# Controller.net
KiCad netlist of a schematic drawn in Altium Designer
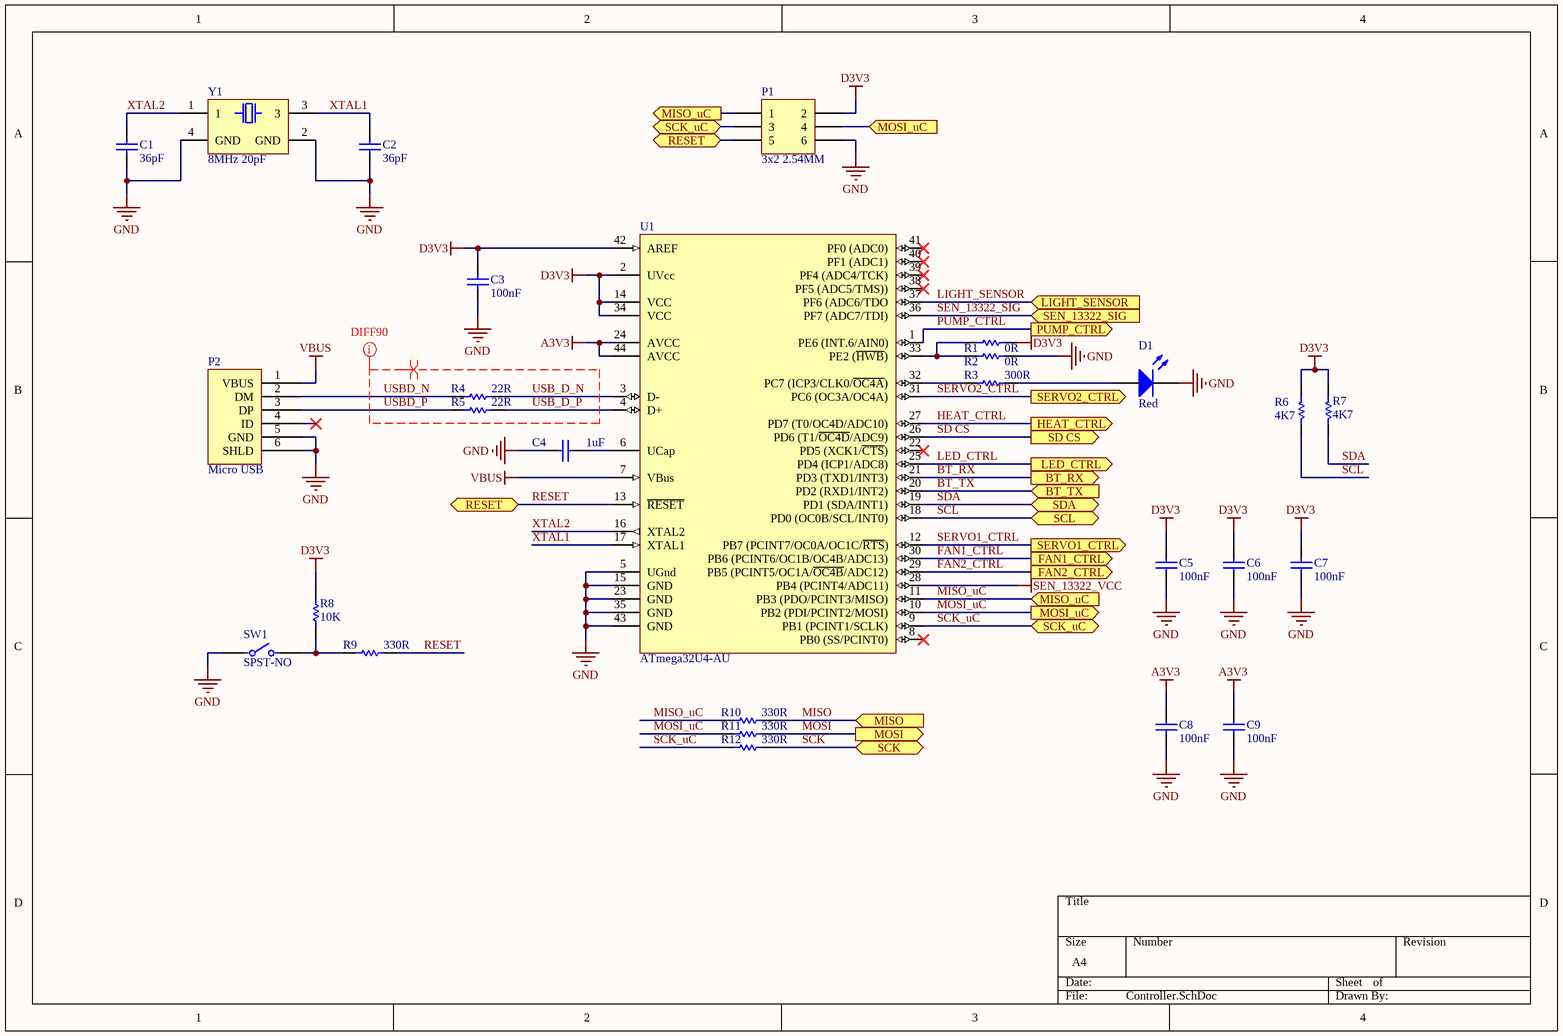
[diagram p0: Controller.SchDoc]

(export (version "E")
  (design (tool "Eeschema 10.0.6"))
  (components
    (comp (ref "C1")
      (value "36pF")
      (footprint "CAP0603")
      (description "Capacitor")
      (fields (field (name "PUBLISHER") "Altium Limited"))
      (libsource (lib "Taiv") (part "Capacitor"))
    )
    (comp (ref "C2")
      (value "36pF")
      (footprint "CAP0603")
      (description "Capacitor")
      (fields (field (name "PUBLISHER") "Altium Limited"))
      (libsource (lib "Taiv") (part "Capacitor"))
    )
    (comp (ref "C3")
      (value "100nF")
      (footprint "CAP0603")
      (description "Capacitor")
      (fields (field (name "PUBLISHER") "Altium Limited"))
      (libsource (lib "Taiv") (part "Capacitor"))
    )
    (comp (ref "C4")
      (value "1uF")
      (footprint "CAP0603")
      (description "Capacitor")
      (fields (field (name "PUBLISHER") "Altium Limited"))
      (libsource (lib "Taiv") (part "Capacitor"))
    )
    (comp (ref "C5")
      (value "100nF")
      (footprint "CAP0603")
      (description "Capacitor")
      (fields (field (name "PUBLISHER") "Altium Limited"))
      (libsource (lib "Taiv") (part "Capacitor"))
    )
    (comp (ref "C6")
      (value "100nF")
      (footprint "CAP0603")
      (description "Capacitor")
      (fields (field (name "PUBLISHER") "Altium Limited"))
      (libsource (lib "Taiv") (part "Capacitor"))
    )
    (comp (ref "C7")
      (value "100nF")
      (footprint "CAP0603")
      (description "Capacitor")
      (fields (field (name "PUBLISHER") "Altium Limited"))
      (libsource (lib "Taiv") (part "Capacitor"))
    )
    (comp (ref "C8")
      (value "100nF")
      (footprint "CAP0603")
      (description "Capacitor")
      (fields (field (name "PUBLISHER") "Altium Limited"))
      (libsource (lib "Taiv") (part "Capacitor"))
    )
    (comp (ref "C9")
      (value "100nF")
      (footprint "CAP0603")
      (description "Capacitor")
      (fields (field (name "PUBLISHER") "Altium Limited"))
      (libsource (lib "Taiv") (part "Capacitor"))
    )
    (comp (ref "D1")
      (value "Red")
      (footprint "DIODE0603")
      (description "Light Emitting Diode")
      (fields (field (name "PUBLISHER") "Altium Limited"))
      (libsource (lib "Taiv") (part "LED"))
    )
    (comp (ref "P1")
      (value "3x2 2.54MM")
      (footprint "HDR2X3")
      (description "Header, 3-Pin, Dual row")
      (fields (field (name "PUBLISHER") "Altium Limited"))
      (libsource (lib "Taiv") (part "3x2 2.54MM"))
    )
    (comp (ref "P2")
      (value "Micro USB")
      (footprint "MOLEX MICRO USB PORT")
      (description "Micro USB Connector")
      (libsource (lib "Taiv") (part "Micro USB Connector"))
    )
    (comp (ref "R1")
      (value "0R")
      (footprint "RES0603")
      (description "Resistor")
      (fields (field (name "PUBLISHER") "Altium Limited"))
      (libsource (lib "Taiv") (part "Resistor"))
    )
    (comp (ref "R2")
      (value "0R")
      (footprint "RES0603")
      (description "Resistor")
      (fields (field (name "PUBLISHER") "Altium Limited"))
      (libsource (lib "Taiv") (part "Resistor"))
    )
    (comp (ref "R3")
      (value "300R")
      (footprint "RES0603")
      (description "Resistor")
      (fields (field (name "PUBLISHER") "Altium Limited"))
      (libsource (lib "Taiv") (part "Resistor"))
    )
    (comp (ref "R4")
      (value "22R")
      (footprint "RES0603")
      (description "Resistor")
      (fields (field (name "PUBLISHER") "Altium Limited"))
      (libsource (lib "Taiv") (part "Resistor"))
    )
    (comp (ref "R5")
      (value "22R")
      (footprint "RES0603")
      (description "Resistor")
      (fields (field (name "PUBLISHER") "Altium Limited"))
      (libsource (lib "Taiv") (part "Resistor"))
    )
    (comp (ref "R6")
      (value "4K7")
      (footprint "RES0603")
      (description "Resistor")
      (fields (field (name "PUBLISHER") "Altium Limited"))
      (libsource (lib "Taiv") (part "Resistor"))
    )
    (comp (ref "R7")
      (value "4K7")
      (footprint "RES0603")
      (description "Resistor")
      (fields (field (name "PUBLISHER") "Altium Limited"))
      (libsource (lib "Taiv") (part "Resistor"))
    )
    (comp (ref "R8")
      (value "10K")
      (footprint "RES0603")
      (description "Resistor")
      (fields (field (name "PUBLISHER") "Altium Limited"))
      (libsource (lib "Taiv") (part "Resistor"))
    )
    (comp (ref "R9")
      (value "330R")
      (footprint "RES0603")
      (description "Resistor")
      (fields (field (name "PUBLISHER") "Altium Limited"))
      (libsource (lib "Taiv") (part "Resistor"))
    )
    (comp (ref "R10")
      (value "330R")
      (footprint "RES0603")
      (description "Resistor")
      (fields (field (name "PUBLISHER") "Altium Limited"))
      (libsource (lib "Taiv") (part "Resistor"))
    )
    (comp (ref "R11")
      (value "330R")
      (footprint "RES0603")
      (description "Resistor")
      (fields (field (name "PUBLISHER") "Altium Limited"))
      (libsource (lib "Taiv") (part "Resistor"))
    )
    (comp (ref "R12")
      (value "330R")
      (footprint "RES0603")
      (description "Resistor")
      (fields (field (name "PUBLISHER") "Altium Limited"))
      (libsource (lib "Taiv") (part "Resistor"))
    )
    (comp (ref "SW1")
      (value "SPST-NO")
      (footprint "Tactile SPST-NO Switch")
      (description "SPST-NO Switch SMD")
      (fields
        (field (name "MANUFACTURER PART NUMBER") "B3U-1000P-B")
        (field (name "OCTOPART") "https://octopart.com/b3u-1000p-b-omron-1057356")
      )
      (libsource (lib "Taiv") (part "B3U-1000P-B"))
    )
    (comp (ref "U1")
      (value "ATmega32U4-AU")
      (footprint "44ML_M")
      (libsource (lib "Altium Content Vault") (part "MC-8B-ATM16U4-SQ44"))
    )
    (comp (ref "Y1")
      (value "8MHz 20pF")
      (footprint "3225 XTAL")
      (description "3225 XTAL")
      (fields (field (name "MP") "TSX-3225 16.0000MF18X-AC3") (field (name "MF") "EPSON"))
      (libsource (lib "Taiv") (part "XTAL"))
    )
  )
  (nets
    (net (code "1") (name "/BT_RX") (class "Default")
      (node (ref "U1") (pin "21") (pinfunction "PD3_(TXD1/INT3)_21") (pintype "bidirectional"))
    )
    (net (code "2") (name "/BT_TX") (class "Default")
      (node (ref "U1") (pin "20") (pinfunction "PD2_(RXD1/INT2)_20") (pintype "bidirectional"))
    )
    (net (code "3") (name "/FAN1_CTRL") (class "Default")
      (node (ref "U1") (pin "30") (pinfunction "PB6_(PCINT6/OC1B/OC4B/ADC13)_30") (pintype "bidirectional"))
    )
    (net (code "4") (name "/FAN2_CTRL") (class "Default")
      (node (ref "U1") (pin "29") (pinfunction "PB5_(PCINT5/OC1A/~{OC4B}/ADC12)_29") (pintype "bidirectional"))
    )
    (net (code "5") (name "/HEAT_CTRL") (class "Default")
      (node (ref "U1") (pin "27") (pinfunction "PD7_(T0/OC4D/ADC10)_27") (pintype "bidirectional"))
    )
    (net (code "6") (name "/LED_CTRL") (class "Default")
      (node (ref "U1") (pin "25") (pinfunction "PD4_(ICP1/ADC8)_25") (pintype "bidirectional"))
    )
    (net (code "7") (name "/LIGHT_SENSOR") (class "Default")
      (node (ref "U1") (pin "37") (pinfunction "PF6_(ADC6/TDO_37") (pintype "bidirectional"))
    )
    (net (code "8") (name "/MISO") (class "Default")
      (node (ref "R10") (pin "1") (pinfunction "1_1") (pintype "passive"))
    )
    (net (code "9") (name "/MISO_uC") (class "Default")
      (node (ref "P1") (pin "1") (pinfunction "1_1") (pintype "passive"))
      (node (ref "R10") (pin "2") (pinfunction "2_2") (pintype "passive"))
      (node (ref "U1") (pin "11") (pinfunction "PB3_(PDO/PCINT3/MISO)_11") (pintype "bidirectional"))
    )
    (net (code "10") (name "/MOSI") (class "Default")
      (node (ref "R11") (pin "1") (pinfunction "1_1") (pintype "passive"))
    )
    (net (code "11") (name "/MOSI_uC") (class "Default")
      (node (ref "P1") (pin "4") (pinfunction "4_4") (pintype "passive"))
      (node (ref "R11") (pin "2") (pinfunction "2_2") (pintype "passive"))
      (node (ref "U1") (pin "10") (pinfunction "PB2_(PDI/PCINT2/MOSI)_10") (pintype "bidirectional"))
    )
    (net (code "12") (name "/PUMP_CTRL") (class "Default")
      (node (ref "U1") (pin "1") (pinfunction "PE6_(INT.6/AIN0)_1") (pintype "bidirectional"))
    )
    (net (code "13") (name "/RESET") (class "Default")
      (node (ref "P1") (pin "5") (pinfunction "5_5") (pintype "passive"))
      (node (ref "R9") (pin "1") (pinfunction "1_1") (pintype "passive"))
      (node (ref "U1") (pin "13") (pinfunction "~{RESET}_13") (pintype "input"))
    )
    (net (code "14") (name "/SCK") (class "Default")
      (node (ref "R12") (pin "1") (pinfunction "1_1") (pintype "passive"))
    )
    (net (code "15") (name "/SCK_uC") (class "Default")
      (node (ref "P1") (pin "3") (pinfunction "3_3") (pintype "passive"))
      (node (ref "R12") (pin "2") (pinfunction "2_2") (pintype "passive"))
      (node (ref "U1") (pin "9") (pinfunction "PB1_(PCINT1/SCLK)_9") (pintype "bidirectional"))
    )
    (net (code "16") (name "/SCL") (class "Default")
      (node (ref "R6") (pin "1") (pinfunction "1_1") (pintype "passive"))
      (node (ref "U1") (pin "18") (pinfunction "PD0_(OC0B/SCL/INT0)_18") (pintype "bidirectional"))
    )
    (net (code "17") (name "/SD CS") (class "Default")
      (node (ref "U1") (pin "26") (pinfunction "PD6_(T1/~{OC4D}/ADC9)_26") (pintype "bidirectional"))
    )
    (net (code "18") (name "/SDA") (class "Default")
      (node (ref "R7") (pin "1") (pinfunction "1_1") (pintype "passive"))
      (node (ref "U1") (pin "19") (pinfunction "PD1_(SDA/INT1)_19") (pintype "bidirectional"))
    )
    (net (code "19") (name "/SEN_13322_SIG") (class "Default")
      (node (ref "U1") (pin "36") (pinfunction "PF7_(ADC7/TDI)_36") (pintype "bidirectional"))
    )
    (net (code "20") (name "/SERVO1_CTRL") (class "Default")
      (node (ref "U1") (pin "12") (pinfunction "PB7_(PCINT7/OC0A/OC1C/~{RTS})_12") (pintype "bidirectional"))
    )
    (net (code "21") (name "/SERVO2_CTRL") (class "Default")
      (node (ref "U1") (pin "31") (pinfunction "PC6_(OC3A/OC4A)_31") (pintype "bidirectional"))
    )
    (net (code "22") (name "/USBD_N") (class "Default")
      (node (ref "P2") (pin "2") (pinfunction "DM_2") (pintype "power_in"))
      (node (ref "R4") (pin "1") (pinfunction "1_1") (pintype "passive"))
    )
    (net (code "23") (name "/USBD_P") (class "Default")
      (node (ref "P2") (pin "3") (pinfunction "DP_3") (pintype "power_in"))
      (node (ref "R5") (pin "1") (pinfunction "1_1") (pintype "passive"))
    )
    (net (code "24") (name "/USB_D_N") (class "Default")
      (node (ref "R4") (pin "2") (pinfunction "2_2") (pintype "passive"))
      (node (ref "U1") (pin "3") (pinfunction "D-_3") (pintype "bidirectional"))
    )
    (net (code "25") (name "/USB_D_P") (class "Default")
      (node (ref "R5") (pin "2") (pinfunction "2_2") (pintype "passive"))
      (node (ref "U1") (pin "4") (pinfunction "D+_4") (pintype "bidirectional"))
    )
    (net (code "26") (name "/XTAL1") (class "Default")
      (node (ref "C2") (pin "2") (pinfunction "2_2") (pintype "passive"))
      (node (ref "U1") (pin "17") (pinfunction "XTAL1_17") (pintype "input"))
      (node (ref "Y1") (pin "3") (pinfunction "3_3") (pintype "passive"))
    )
    (net (code "27") (name "/XTAL2") (class "Default")
      (node (ref "C1") (pin "2") (pinfunction "2_2") (pintype "passive"))
      (node (ref "U1") (pin "16") (pinfunction "XTAL2_16") (pintype "output"))
      (node (ref "Y1") (pin "1") (pinfunction "1_1") (pintype "passive"))
    )
    (net (code "28") (name "A3V3") (class "Default")
      (node (ref "C8") (pin "2") (pinfunction "2_2") (pintype "passive"))
      (node (ref "C9") (pin "2") (pinfunction "2_2") (pintype "passive"))
      (node (ref "U1") (pin "24") (pinfunction "AVCC_24") (pintype "power_in"))
      (node (ref "U1") (pin "44") (pinfunction "AVCC_44") (pintype "power_in"))
    )
    (net (code "29") (name "D3V3") (class "Default")
      (node (ref "C3") (pin "2") (pinfunction "2_2") (pintype "passive"))
      (node (ref "C5") (pin "2") (pinfunction "2_2") (pintype "passive"))
      (node (ref "C6") (pin "2") (pinfunction "2_2") (pintype "passive"))
      (node (ref "C7") (pin "2") (pinfunction "2_2") (pintype "passive"))
      (node (ref "P1") (pin "2") (pinfunction "2_2") (pintype "passive"))
      (node (ref "R1") (pin "2") (pinfunction "2_2") (pintype "passive"))
      (node (ref "R6") (pin "2") (pinfunction "2_2") (pintype "passive"))
      (node (ref "R7") (pin "2") (pinfunction "2_2") (pintype "passive"))
      (node (ref "R8") (pin "2") (pinfunction "2_2") (pintype "passive"))
      (node (ref "U1") (pin "14") (pinfunction "VCC_14") (pintype "power_in"))
      (node (ref "U1") (pin "2") (pinfunction "UVcc_2") (pintype "power_in"))
      (node (ref "U1") (pin "34") (pinfunction "VCC_34") (pintype "power_in"))
      (node (ref "U1") (pin "42") (pinfunction "AREF_42") (pintype "input"))
    )
    (net (code "30") (name "GND") (class "Default")
      (node (ref "C1") (pin "1") (pinfunction "1_1") (pintype "passive"))
      (node (ref "C2") (pin "1") (pinfunction "1_1") (pintype "passive"))
      (node (ref "C3") (pin "1") (pinfunction "1_1") (pintype "passive"))
      (node (ref "C4") (pin "1") (pinfunction "1_1") (pintype "passive"))
      (node (ref "C5") (pin "1") (pinfunction "1_1") (pintype "passive"))
      (node (ref "C6") (pin "1") (pinfunction "1_1") (pintype "passive"))
      (node (ref "C7") (pin "1") (pinfunction "1_1") (pintype "passive"))
      (node (ref "C8") (pin "1") (pinfunction "1_1") (pintype "passive"))
      (node (ref "C9") (pin "1") (pinfunction "1_1") (pintype "passive"))
      (node (ref "D1") (pin "2") (pinfunction "K_2") (pintype "passive"))
      (node (ref "P1") (pin "6") (pinfunction "6_6") (pintype "passive"))
      (node (ref "P2") (pin "5") (pinfunction "GND_5") (pintype "power_in"))
      (node (ref "P2") (pin "6") (pinfunction "SHLD_6") (pintype "power_in"))
      (node (ref "R2") (pin "2") (pinfunction "2_2") (pintype "passive"))
      (node (ref "SW1") (pin "1") (pinfunction "1_1") (pintype "passive"))
      (node (ref "U1") (pin "15") (pinfunction "GND_15") (pintype "power_in"))
      (node (ref "U1") (pin "23") (pinfunction "GND_23") (pintype "power_in"))
      (node (ref "U1") (pin "35") (pinfunction "GND_35") (pintype "power_in"))
      (node (ref "U1") (pin "43") (pinfunction "GND_43") (pintype "power_in"))
      (node (ref "U1") (pin "5") (pinfunction "UGnd_5") (pintype "power_in"))
      (node (ref "Y1") (pin "2") (pinfunction "GND_2") (pintype "power_in"))
      (node (ref "Y1") (pin "4") (pinfunction "GND_4") (pintype "power_in"))
    )
    (net (code "31") (name "Net-(D1-A)") (class "Default")
      (node (ref "D1") (pin "1") (pinfunction "A_1") (pintype "passive"))
      (node (ref "R3") (pin "1") (pinfunction "1_1") (pintype "passive"))
    )
    (net (code "32") (name "Net-(R8-Pad1)") (class "Default")
      (node (ref "R8") (pin "1") (pinfunction "1_1") (pintype "passive"))
      (node (ref "R9") (pin "2") (pinfunction "2_2") (pintype "passive"))
      (node (ref "SW1") (pin "2") (pinfunction "2_2") (pintype "passive"))
    )
    (net (code "33") (name "Net-(U1-PC7_(ICP3{slash}CLK0{slash}~{OC4A}))") (class "Default")
      (node (ref "R3") (pin "2") (pinfunction "2_2") (pintype "passive"))
      (node (ref "U1") (pin "32") (pinfunction "PC7_(ICP3/CLK0/~{OC4A})_32") (pintype "bidirectional"))
    )
    (net (code "34") (name "Net-(U1-PE2_(~{HWB}))") (class "Default")
      (node (ref "R1") (pin "1") (pinfunction "1_1") (pintype "passive"))
      (node (ref "R2") (pin "1") (pinfunction "1_1") (pintype "passive"))
      (node (ref "U1") (pin "33") (pinfunction "PE2_(~{HWB})_33") (pintype "bidirectional"))
    )
    (net (code "35") (name "Net-(U1-UCap)") (class "Default")
      (node (ref "C4") (pin "2") (pinfunction "2_2") (pintype "passive"))
      (node (ref "U1") (pin "6") (pinfunction "UCap_6") (pintype "passive"))
    )
    (net (code "36") (name "SEN_13322_VCC") (class "Default")
      (node (ref "U1") (pin "28") (pinfunction "PB4_(PCINT4/ADC11)_28") (pintype "bidirectional"))
    )
    (net (code "37") (name "VBUS") (class "Default")
      (node (ref "P2") (pin "1") (pinfunction "VBUS_1") (pintype "power_in"))
      (node (ref "U1") (pin "7") (pinfunction "VBus_7") (pintype "input"))
    )
    (net (code "38") (name "unconnected-(P2-ID-Pad4)") (class "Default")
      (node (ref "P2") (pin "4") (pinfunction "ID_4") (pintype "power_in+no_connect"))
    )
    (net (code "39") (name "unconnected-(U1-PB0_(SS{slash}PCINT0)-Pad8)") (class "Default")
      (node (ref "U1") (pin "8") (pinfunction "PB0_(SS/PCINT0)_8") (pintype "bidirectional+no_connect"))
    )
    (net (code "40") (name "unconnected-(U1-PD5_(XCK1{slash}~{CTS})-Pad22)") (class "Default")
      (node (ref "U1") (pin "22") (pinfunction "PD5_(XCK1/~{CTS})_22") (pintype "bidirectional+no_connect"))
    )
    (net (code "41") (name "unconnected-(U1-PF0_(ADC0)-Pad41)") (class "Default")
      (node (ref "U1") (pin "41") (pinfunction "PF0_(ADC0)_41") (pintype "bidirectional+no_connect"))
    )
    (net (code "42") (name "unconnected-(U1-PF1_(ADC1)-Pad40)") (class "Default")
      (node (ref "U1") (pin "40") (pinfunction "PF1_(ADC1)_40") (pintype "bidirectional+no_connect"))
    )
    (net (code "43") (name "unconnected-(U1-PF4_(ADC4{slash}TCK)-Pad39)") (class "Default")
      (node (ref "U1") (pin "39") (pinfunction "PF4_(ADC4/TCK)_39") (pintype "bidirectional+no_connect"))
    )
    (net (code "44") (name "unconnected-(U1-PF5_(ADC5{slash}TMS))-Pad38)") (class "Default")
      (node (ref "U1") (pin "38") (pinfunction "PF5_(ADC5/TMS))_38") (pintype "bidirectional+no_connect"))
    )
  )
)
